# BrauV2_AnalogueOutput.net
KiCad netlist of a schematic drawn in Altium Designer
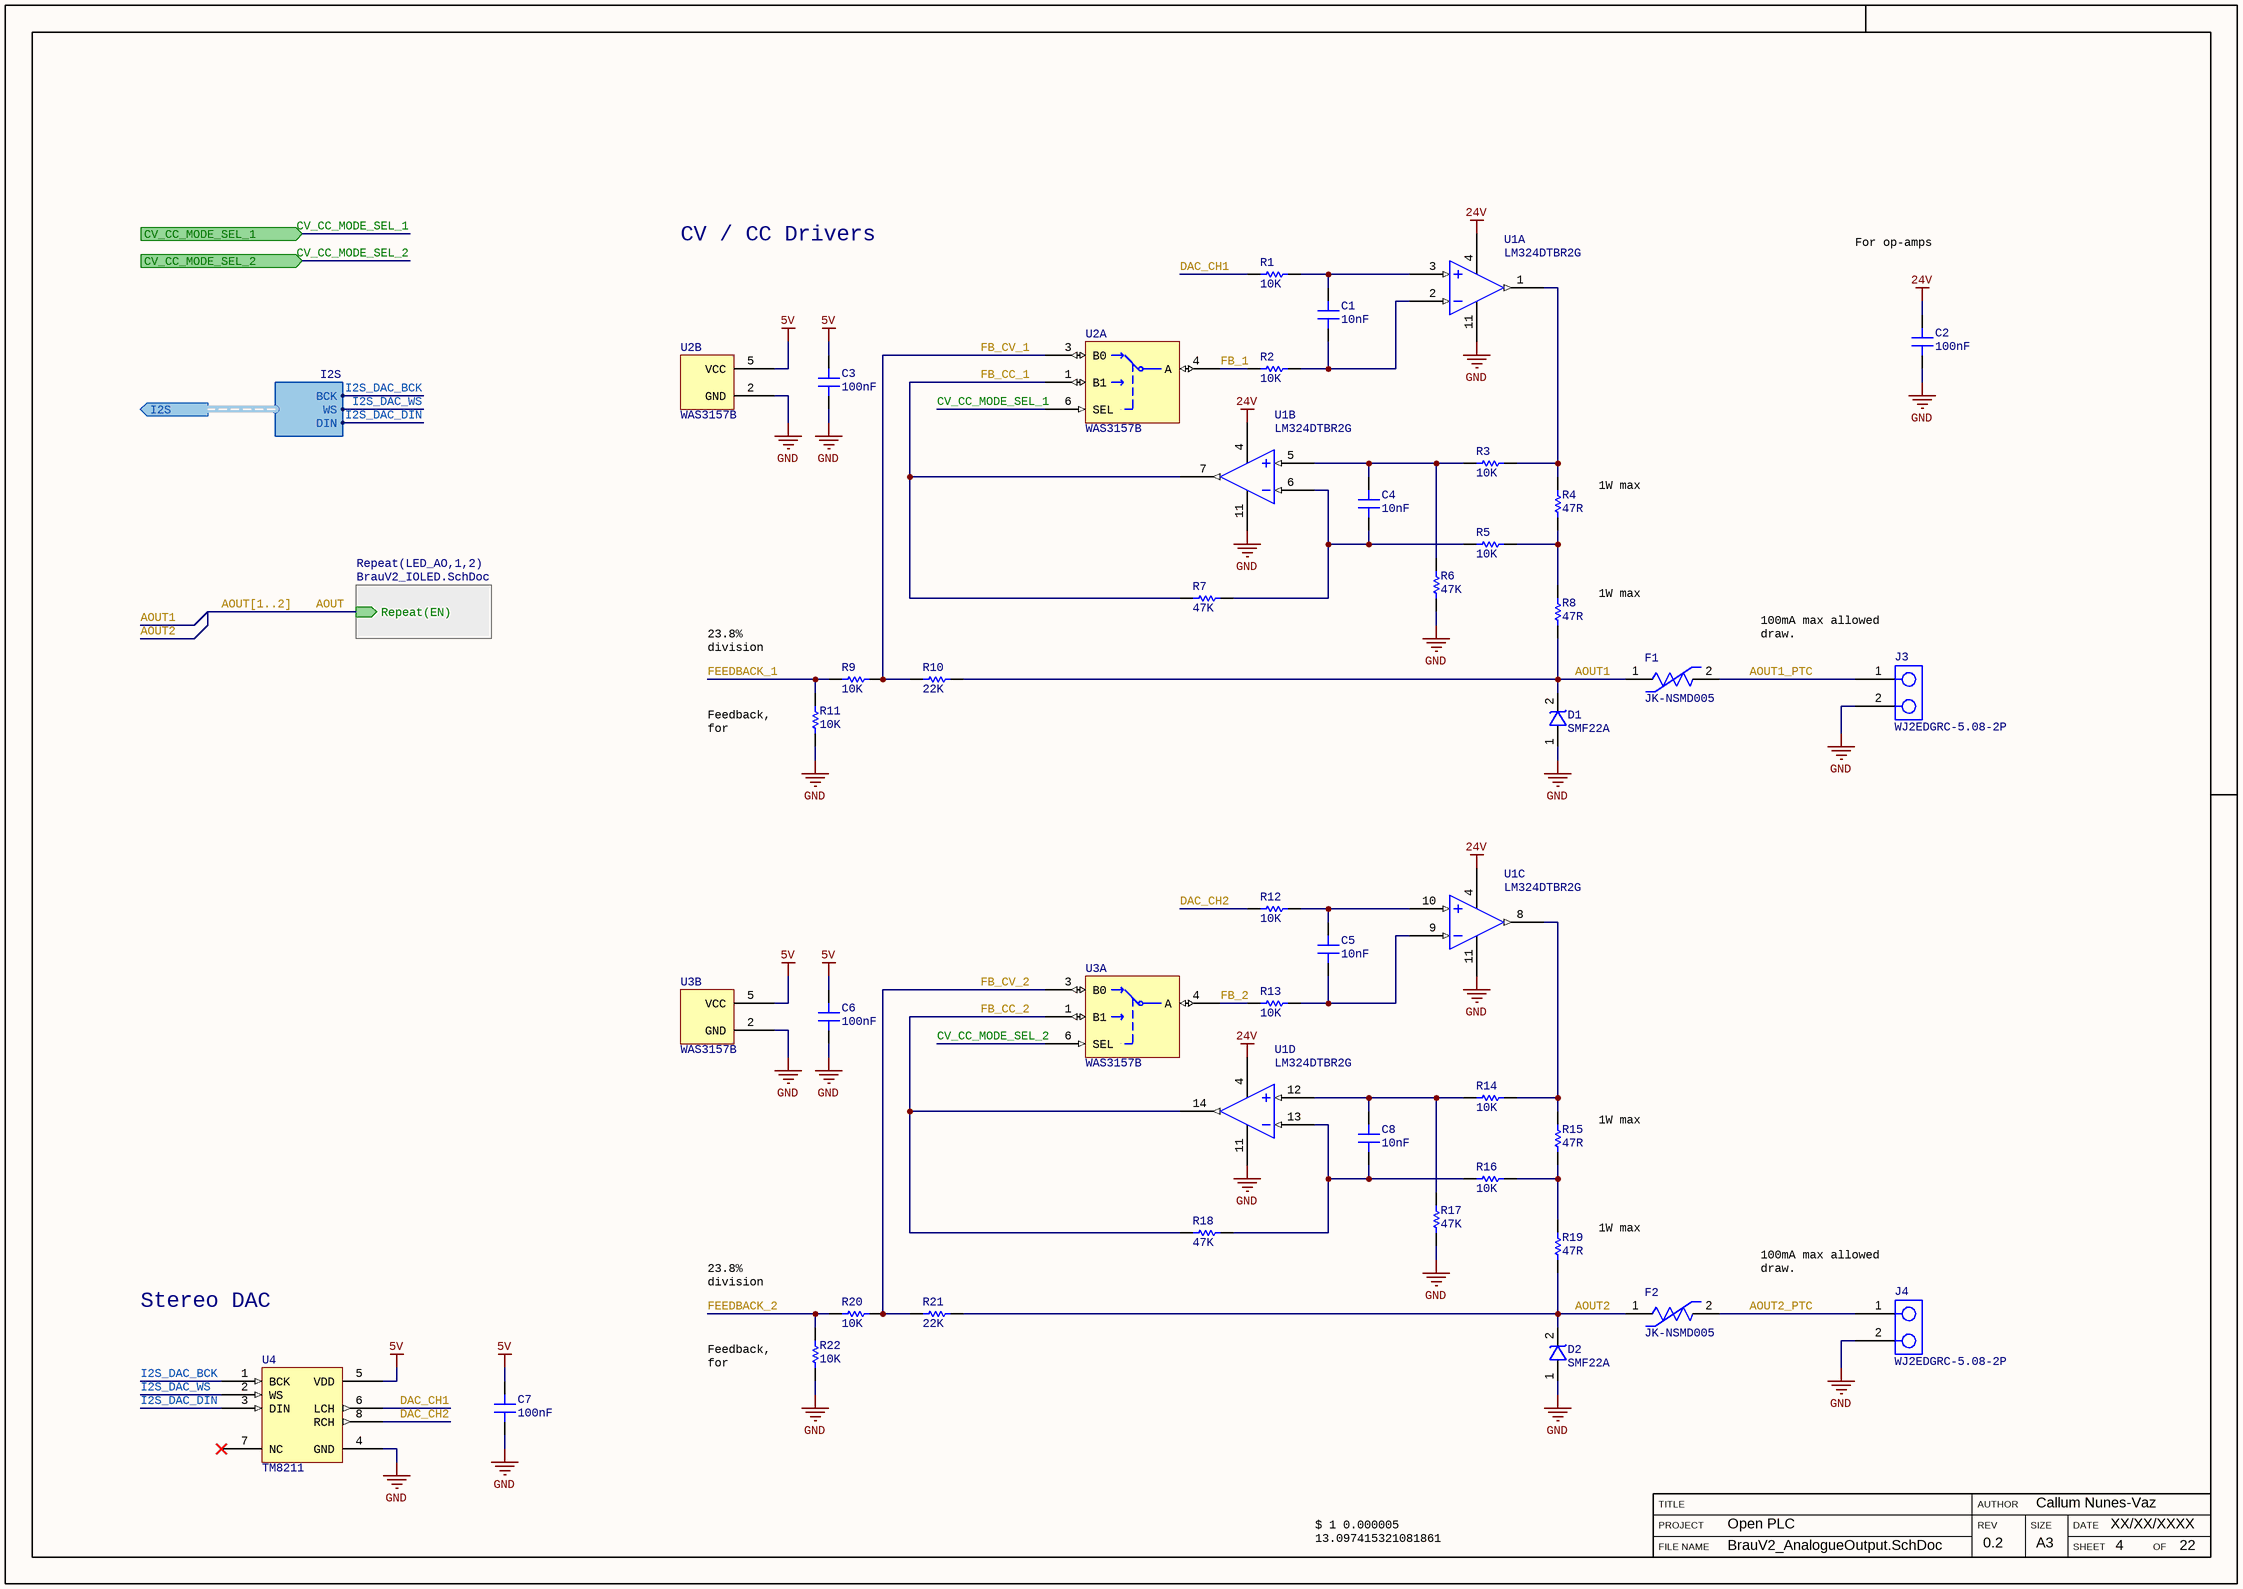
[diagram p0: BrauV2_AnalogueOutput.SchDoc]

(export (version "E")
  (design (tool "Eeschema 10.0.6"))
  (components
    (comp (ref "C1")
      (value "CC0402KRX7R9BB103")
      (footprint "SMD_CAP_0402(1005)_N")
      (description "10nF ±10% 50V X7R 0402 Multilayer Ceramic Capacitors MLCC - SMD/SMT RoHS")
      (fields (field (name "TOLERANCE") "10%") (field (name "CAPACITANCE") "10nF"))
      (libsource (lib "BrauV2_Capacitor") (part "10nF 0402 50V 10%"))
    )
    (comp (ref "C2")
      (value "CC0402KRX5R9BB104")
      (footprint "SMD_CAP_0402(1005)_N")
      (description "100nF ±10% 50V X5R 0402 Multilayer Ceramic Capacitors MLCC - SMD/SMT RoHS")
      (fields (field (name "TOLERANCE") "10%") (field (name "CAPACITANCE") "100nF"))
      (libsource (lib "BrauV2_Capacitor") (part "100nF 0402 50V 10%"))
    )
    (comp (ref "C3")
      (value "CC0402KRX5R6BB104")
      (footprint "SMD_CAP_0402(1005)_N")
      (description "100nF ±10% 10V X5R 0402 Multilayer Ceramic Capacitors MLCC - SMD/SMT RoHS")
      (fields (field (name "TOLERANCE") "10%") (field (name "CAPACITANCE") "100nF"))
      (libsource (lib "BrauV2_Capacitor") (part "100nF 0402 10V 10%"))
    )
    (comp (ref "C4")
      (value "CC0402KRX7R9BB103")
      (footprint "SMD_CAP_0402(1005)_N")
      (description "10nF ±10% 50V X7R 0402 Multilayer Ceramic Capacitors MLCC - SMD/SMT RoHS")
      (fields (field (name "TOLERANCE") "10%") (field (name "CAPACITANCE") "10nF"))
      (libsource (lib "BrauV2_Capacitor") (part "10nF 0402 50V 10%"))
    )
    (comp (ref "C5")
      (value "CC0402KRX7R9BB103")
      (footprint "SMD_CAP_0402(1005)_N")
      (description "10nF ±10% 50V X7R 0402 Multilayer Ceramic Capacitors MLCC - SMD/SMT RoHS")
      (fields (field (name "TOLERANCE") "10%") (field (name "CAPACITANCE") "10nF"))
      (libsource (lib "BrauV2_Capacitor") (part "10nF 0402 50V 10%"))
    )
    (comp (ref "C6")
      (value "CC0402KRX5R6BB104")
      (footprint "SMD_CAP_0402(1005)_N")
      (description "100nF ±10% 10V X5R 0402 Multilayer Ceramic Capacitors MLCC - SMD/SMT RoHS")
      (fields (field (name "TOLERANCE") "10%") (field (name "CAPACITANCE") "100nF"))
      (libsource (lib "BrauV2_Capacitor") (part "100nF 0402 10V 10%"))
    )
    (comp (ref "C7")
      (value "CC0402KRX5R6BB104")
      (footprint "SMD_CAP_0402(1005)_N")
      (description "100nF ±10% 10V X5R 0402 Multilayer Ceramic Capacitors MLCC - SMD/SMT RoHS")
      (fields (field (name "TOLERANCE") "10%") (field (name "CAPACITANCE") "100nF"))
      (libsource (lib "BrauV2_Capacitor") (part "100nF 0402 10V 10%"))
    )
    (comp (ref "C8")
      (value "CC0402KRX7R9BB103")
      (footprint "SMD_CAP_0402(1005)_N")
      (description "10nF ±10% 50V X7R 0402 Multilayer Ceramic Capacitors MLCC - SMD/SMT RoHS")
      (fields (field (name "TOLERANCE") "10%") (field (name "CAPACITANCE") "10nF"))
      (libsource (lib "BrauV2_Capacitor") (part "10nF 0402 50V 10%"))
    )
    (comp (ref "D1")
      (value "SMF22A")
      (footprint "SOD-123FL")
      (description "Unidirectional 22V 24.4V 35.5V 5.6A SOD-123F TVS RoHS")
      (libsource (lib "BrauV2") (part "SMF22A"))
    )
    (comp (ref "D2")
      (value "SMF22A")
      (footprint "SOD-123FL")
      (description "Unidirectional 22V 24.4V 35.5V 5.6A SOD-123F TVS RoHS")
      (libsource (lib "BrauV2") (part "SMF22A"))
    )
    (comp (ref "F1")
      (value "JK-NSMD005")
      (footprint "SMD_RES_1206(3216)_N")
      (description "60V 150mA 1.5s 1206 PTC Resettable Fuses RoHS")
      (libsource (lib "BrauV2_Resistor") (part "JK-NSMD005"))
    )
    (comp (ref "F2")
      (value "JK-NSMD005")
      (footprint "SMD_RES_1206(3216)_N")
      (description "60V 150mA 1.5s 1206 PTC Resettable Fuses RoHS")
      (libsource (lib "BrauV2_Resistor") (part "JK-NSMD005"))
    )
    (comp (ref "J3")
      (value "WJ2EDGRC-5.08-2P")
      (footprint "796638-2")
      (description "Covered（4Sided） 2 1 0.200\"（5.08mm） 2 P=5.08mm Pluggable System Terminal Block RoHS")
      (libsource (lib "BrauV2_Connector") (part "WJ2EDGRC-5.08-2P"))
    )
    (comp (ref "J4")
      (value "WJ2EDGRC-5.08-2P")
      (footprint "796638-2")
      (description "Covered（4Sided） 2 1 0.200\"（5.08mm） 2 P=5.08mm Pluggable System Terminal Block RoHS")
      (libsource (lib "BrauV2_Connector") (part "WJ2EDGRC-5.08-2P"))
    )
    (comp (ref "R1")
      (value "RC0402FR-0710KL")
      (footprint "SMD_RES_0402(1005)_N")
      (description "10kΩ ±1% 1/16W ±100ppm/℃ 0402 Chip Resistor - Surface Mount RoHS")
      (fields (field (name "TOLERANCE") "1%") (field (name "RESISTANCE") "10K"))
      (libsource (lib "BrauV2_Resistor") (part "10K 0402 1% 1/16W"))
    )
    (comp (ref "R2")
      (value "RC0402FR-0710KL")
      (footprint "SMD_RES_0402(1005)_N")
      (description "10kΩ ±1% 1/16W ±100ppm/℃ 0402 Chip Resistor - Surface Mount RoHS")
      (fields (field (name "TOLERANCE") "1%") (field (name "RESISTANCE") "10K"))
      (libsource (lib "BrauV2_Resistor") (part "10K 0402 1% 1/16W"))
    )
    (comp (ref "R3")
      (value "RC0402FR-0710KL")
      (footprint "SMD_RES_0402(1005)_N")
      (description "10kΩ ±1% 1/16W ±100ppm/℃ 0402 Chip Resistor - Surface Mount RoHS")
      (fields (field (name "TOLERANCE") "1%") (field (name "RESISTANCE") "10K"))
      (libsource (lib "BrauV2_Resistor") (part "10K 0402 1% 1/16W"))
    )
    (comp (ref "R4")
      (value "AC2512FK-0747RL")
      (footprint "SMD_RES_2512(6432)_N")
      (description "47Ω ±1% 1W ±100ppm/℃ 2512 Chip Resistor - Surface Mount RoHS")
      (fields (field (name "TOLERANCE") "1%") (field (name "RESISTANCE") "47R"))
      (libsource (lib "BrauV2_Resistor") (part "47R 2512 1% 1W"))
    )
    (comp (ref "R5")
      (value "RC0402FR-0710KL")
      (footprint "SMD_RES_0402(1005)_N")
      (description "10kΩ ±1% 1/16W ±100ppm/℃ 0402 Chip Resistor - Surface Mount RoHS")
      (fields (field (name "TOLERANCE") "1%") (field (name "RESISTANCE") "10K"))
      (libsource (lib "BrauV2_Resistor") (part "10K 0402 1% 1/16W"))
    )
    (comp (ref "R6")
      (value "RC0402FR-0747KL")
      (footprint "SMD_RES_0402(1005)_N")
      (description "47kΩ ±1% 1/16W ±100ppm/℃ 0402 Chip Resistor - Surface Mount RoHS")
      (fields (field (name "TOLERANCE") "1%") (field (name "RESISTANCE") "47K"))
      (libsource (lib "BrauV2_Resistor") (part "47K 0402 1% 1/16W"))
    )
    (comp (ref "R7")
      (value "RC0402FR-0747KL")
      (footprint "SMD_RES_0402(1005)_N")
      (description "47kΩ ±1% 1/16W ±100ppm/℃ 0402 Chip Resistor - Surface Mount RoHS")
      (fields (field (name "TOLERANCE") "1%") (field (name "RESISTANCE") "47K"))
      (libsource (lib "BrauV2_Resistor") (part "47K 0402 1% 1/16W"))
    )
    (comp (ref "R8")
      (value "AC2512FK-0747RL")
      (footprint "SMD_RES_2512(6432)_N")
      (description "47Ω ±1% 1W ±100ppm/℃ 2512 Chip Resistor - Surface Mount RoHS")
      (fields (field (name "TOLERANCE") "1%") (field (name "RESISTANCE") "47R"))
      (libsource (lib "BrauV2_Resistor") (part "47R 2512 1% 1W"))
    )
    (comp (ref "R9")
      (value "RC0402FR-0710KL")
      (footprint "SMD_RES_0402(1005)_N")
      (description "10kΩ ±1% 1/16W ±100ppm/℃ 0402 Chip Resistor - Surface Mount RoHS")
      (fields (field (name "TOLERANCE") "1%") (field (name "RESISTANCE") "10K"))
      (libsource (lib "BrauV2_Resistor") (part "10K 0402 1% 1/16W"))
    )
    (comp (ref "R10")
      (value "RC0402FR-0722KL")
      (footprint "SMD_RES_0402(1005)_N")
      (description "22kΩ ±1% 1/16W ±100ppm/℃ 0402 Chip Resistor - Surface Mount RoHS")
      (fields (field (name "TOLERANCE") "1%") (field (name "RESISTANCE") "22K"))
      (libsource (lib "BrauV2_Resistor") (part "22K 0402 1% 1/16W"))
    )
    (comp (ref "R11")
      (value "RC0402FR-0710KL")
      (footprint "SMD_RES_0402(1005)_N")
      (description "10kΩ ±1% 1/16W ±100ppm/℃ 0402 Chip Resistor - Surface Mount RoHS")
      (fields (field (name "TOLERANCE") "1%") (field (name "RESISTANCE") "10K"))
      (libsource (lib "BrauV2_Resistor") (part "10K 0402 1% 1/16W"))
    )
    (comp (ref "R12")
      (value "RC0402FR-0710KL")
      (footprint "SMD_RES_0402(1005)_N")
      (description "10kΩ ±1% 1/16W ±100ppm/℃ 0402 Chip Resistor - Surface Mount RoHS")
      (fields (field (name "TOLERANCE") "1%") (field (name "RESISTANCE") "10K"))
      (libsource (lib "BrauV2_Resistor") (part "10K 0402 1% 1/16W"))
    )
    (comp (ref "R13")
      (value "RC0402FR-0710KL")
      (footprint "SMD_RES_0402(1005)_N")
      (description "10kΩ ±1% 1/16W ±100ppm/℃ 0402 Chip Resistor - Surface Mount RoHS")
      (fields (field (name "TOLERANCE") "1%") (field (name "RESISTANCE") "10K"))
      (libsource (lib "BrauV2_Resistor") (part "10K 0402 1% 1/16W"))
    )
    (comp (ref "R14")
      (value "RC0402FR-0710KL")
      (footprint "SMD_RES_0402(1005)_N")
      (description "10kΩ ±1% 1/16W ±100ppm/℃ 0402 Chip Resistor - Surface Mount RoHS")
      (fields (field (name "TOLERANCE") "1%") (field (name "RESISTANCE") "10K"))
      (libsource (lib "BrauV2_Resistor") (part "10K 0402 1% 1/16W"))
    )
    (comp (ref "R15")
      (value "AC2512FK-0747RL")
      (footprint "SMD_RES_2512(6432)_N")
      (description "47Ω ±1% 1W ±100ppm/℃ 2512 Chip Resistor - Surface Mount RoHS")
      (fields (field (name "TOLERANCE") "1%") (field (name "RESISTANCE") "47R"))
      (libsource (lib "BrauV2_Resistor") (part "47R 2512 1% 1W"))
    )
    (comp (ref "R16")
      (value "RC0402FR-0710KL")
      (footprint "SMD_RES_0402(1005)_N")
      (description "10kΩ ±1% 1/16W ±100ppm/℃ 0402 Chip Resistor - Surface Mount RoHS")
      (fields (field (name "TOLERANCE") "1%") (field (name "RESISTANCE") "10K"))
      (libsource (lib "BrauV2_Resistor") (part "10K 0402 1% 1/16W"))
    )
    (comp (ref "R17")
      (value "RC0402FR-0747KL")
      (footprint "SMD_RES_0402(1005)_N")
      (description "47kΩ ±1% 1/16W ±100ppm/℃ 0402 Chip Resistor - Surface Mount RoHS")
      (fields (field (name "TOLERANCE") "1%") (field (name "RESISTANCE") "47K"))
      (libsource (lib "BrauV2_Resistor") (part "47K 0402 1% 1/16W"))
    )
    (comp (ref "R18")
      (value "RC0402FR-0747KL")
      (footprint "SMD_RES_0402(1005)_N")
      (description "47kΩ ±1% 1/16W ±100ppm/℃ 0402 Chip Resistor - Surface Mount RoHS")
      (fields (field (name "TOLERANCE") "1%") (field (name "RESISTANCE") "47K"))
      (libsource (lib "BrauV2_Resistor") (part "47K 0402 1% 1/16W"))
    )
    (comp (ref "R19")
      (value "AC2512FK-0747RL")
      (footprint "SMD_RES_2512(6432)_N")
      (description "47Ω ±1% 1W ±100ppm/℃ 2512 Chip Resistor - Surface Mount RoHS")
      (fields (field (name "TOLERANCE") "1%") (field (name "RESISTANCE") "47R"))
      (libsource (lib "BrauV2_Resistor") (part "47R 2512 1% 1W"))
    )
    (comp (ref "R20")
      (value "RC0402FR-0710KL")
      (footprint "SMD_RES_0402(1005)_N")
      (description "10kΩ ±1% 1/16W ±100ppm/℃ 0402 Chip Resistor - Surface Mount RoHS")
      (fields (field (name "TOLERANCE") "1%") (field (name "RESISTANCE") "10K"))
      (libsource (lib "BrauV2_Resistor") (part "10K 0402 1% 1/16W"))
    )
    (comp (ref "R21")
      (value "RC0402FR-0722KL")
      (footprint "SMD_RES_0402(1005)_N")
      (description "22kΩ ±1% 1/16W ±100ppm/℃ 0402 Chip Resistor - Surface Mount RoHS")
      (fields (field (name "TOLERANCE") "1%") (field (name "RESISTANCE") "22K"))
      (libsource (lib "BrauV2_Resistor") (part "22K 0402 1% 1/16W"))
    )
    (comp (ref "R22")
      (value "RC0402FR-0710KL")
      (footprint "SMD_RES_0402(1005)_N")
      (description "10kΩ ±1% 1/16W ±100ppm/℃ 0402 Chip Resistor - Surface Mount RoHS")
      (fields (field (name "TOLERANCE") "1%") (field (name "RESISTANCE") "10K"))
      (libsource (lib "BrauV2_Resistor") (part "10K 0402 1% 1/16W"))
    )
    (comp (ref "U1")
      (value "LM324DTBR2G")
      (footprint "TSSOP-14")
      (description "General Purpose 4 3V ~ 32V, ±1.5V ~ 16V 1MHz 0.6 V/us TSSOP-14 Operational Amplifiers RoHS")
      (libsource (lib "BrauV2_IC") (part "LM324DTBR2G"))
    )
    (comp (ref "U2")
      (value "WAS3157B")
      (footprint "SOT23-6")
      (description "5.5Ω, 400MHz Bandwidth, SPDT Analog Switch SOT23-6")
      (libsource (lib "BrauV2_IC") (part "WAS3157B"))
    )
    (comp (ref "U3")
      (value "WAS3157B")
      (footprint "SOT23-6")
      (description "5.5Ω, 400MHz Bandwidth, SPDT Analog Switch SOT23-6")
      (libsource (lib "BrauV2_IC") (part "WAS3157B"))
    )
    (comp (ref "U4")
      (value "TM8211")
      (footprint "SOIC-8-3.9mm")
      (description "Digital To Analog Converters (DACs) 16bit I2S")
      (libsource (lib "BrauV2_IC") (part "TM8211"))
    )
  )
  (nets
    (net (code "3") (name "/AOUT1") (class "Default")
      (node (ref "D1") (pin "2") (pinfunction "CATHODE_2") (pintype "passive"))
      (node (ref "F1") (pin "1") (pinfunction "1_1") (pintype "passive"))
      (node (ref "R10") (pin "2") (pinfunction "2_2") (pintype "passive"))
      (node (ref "R8") (pin "1") (pinfunction "1_1") (pintype "passive"))
    )
    (net (code "4") (name "/AOUT1_PTC") (class "Default")
      (node (ref "F1") (pin "2") (pinfunction "2_2") (pintype "passive"))
      (node (ref "J3") (pin "1") (pinfunction "1_1") (pintype "passive"))
    )
    (net (code "5") (name "/AOUT2") (class "Default")
      (node (ref "D2") (pin "2") (pinfunction "CATHODE_2") (pintype "passive"))
      (node (ref "F2") (pin "1") (pinfunction "1_1") (pintype "passive"))
      (node (ref "R19") (pin "1") (pinfunction "1_1") (pintype "passive"))
      (node (ref "R21") (pin "2") (pinfunction "2_2") (pintype "passive"))
    )
    (net (code "6") (name "/AOUT2_PTC") (class "Default")
      (node (ref "F2") (pin "2") (pinfunction "2_2") (pintype "passive"))
      (node (ref "J4") (pin "1") (pinfunction "1_1") (pintype "passive"))
    )
    (net (code "8") (name "/CV_CC_MODE_SEL_1") (class "Default")
      (node (ref "U2") (pin "6") (pinfunction "SEL_6") (pintype "input"))
    )
    (net (code "9") (name "/CV_CC_MODE_SEL_2") (class "Default")
      (node (ref "U3") (pin "6") (pinfunction "SEL_6") (pintype "input"))
    )
    (net (code "10") (name "/DAC_CH1") (class "Default")
      (node (ref "R1") (pin "1") (pinfunction "1_1") (pintype "passive"))
      (node (ref "U4") (pin "6") (pinfunction "LCH_6") (pintype "output"))
    )
    (net (code "11") (name "/DAC_CH2") (class "Default")
      (node (ref "R12") (pin "1") (pinfunction "1_1") (pintype "passive"))
      (node (ref "U4") (pin "8") (pinfunction "RCH_8") (pintype "output"))
    )
    (net (code "12") (name "/FB_1") (class "Default")
      (node (ref "R2") (pin "1") (pinfunction "1_1") (pintype "passive"))
      (node (ref "U2") (pin "4") (pinfunction "A_4") (pintype "bidirectional"))
    )
    (net (code "13") (name "/FB_2") (class "Default")
      (node (ref "R13") (pin "1") (pinfunction "1_1") (pintype "passive"))
      (node (ref "U3") (pin "4") (pinfunction "A_4") (pintype "bidirectional"))
    )
    (net (code "14") (name "/FB_CC_1") (class "Default")
      (node (ref "R7") (pin "1") (pinfunction "1_1") (pintype "passive"))
      (node (ref "U1") (pin "7") (pinfunction "VOUT_7") (pintype "output"))
      (node (ref "U2") (pin "1") (pinfunction "B1_1") (pintype "bidirectional"))
    )
    (net (code "15") (name "/FB_CC_2") (class "Default")
      (node (ref "R18") (pin "1") (pinfunction "1_1") (pintype "passive"))
      (node (ref "U1") (pin "14") (pinfunction "VOUT_14") (pintype "output"))
      (node (ref "U3") (pin "1") (pinfunction "B1_1") (pintype "bidirectional"))
    )
    (net (code "16") (name "/FB_CV_1") (class "Default")
      (node (ref "R10") (pin "1") (pinfunction "1_1") (pintype "passive"))
      (node (ref "R9") (pin "1") (pinfunction "1_1") (pintype "passive"))
      (node (ref "U2") (pin "3") (pinfunction "B0_3") (pintype "bidirectional"))
    )
    (net (code "17") (name "/FB_CV_2") (class "Default")
      (node (ref "R20") (pin "1") (pinfunction "1_1") (pintype "passive"))
      (node (ref "R21") (pin "1") (pinfunction "1_1") (pintype "passive"))
      (node (ref "U3") (pin "3") (pinfunction "B0_3") (pintype "bidirectional"))
    )
    (net (code "18") (name "/FEEDBACK_1") (class "Default")
      (node (ref "R11") (pin "2") (pinfunction "2_2") (pintype "passive"))
      (node (ref "R9") (pin "2") (pinfunction "2_2") (pintype "passive"))
    )
    (net (code "19") (name "/FEEDBACK_2") (class "Default")
      (node (ref "R20") (pin "2") (pinfunction "2_2") (pintype "passive"))
      (node (ref "R22") (pin "2") (pinfunction "2_2") (pintype "passive"))
    )
    (net (code "20") (name "/I2S_DAC_BCK") (class "Default")
      (node (ref "U4") (pin "1") (pinfunction "BCK_1") (pintype "input"))
    )
    (net (code "21") (name "/I2S_DAC_DIN") (class "Default")
      (node (ref "U4") (pin "3") (pinfunction "DIN_3") (pintype "input"))
    )
    (net (code "22") (name "/I2S_DAC_WS") (class "Default")
      (node (ref "U4") (pin "2") (pinfunction "WS_2") (pintype "input"))
    )
    (net (code "24") (name "5V") (class "Default")
      (node (ref "C3") (pin "2") (pinfunction "2_2") (pintype "passive"))
      (node (ref "C6") (pin "2") (pinfunction "2_2") (pintype "passive"))
      (node (ref "C7") (pin "2") (pinfunction "2_2") (pintype "passive"))
      (node (ref "U2") (pin "5") (pinfunction "VCC_5") (pintype "power_in"))
      (node (ref "U3") (pin "5") (pinfunction "VCC_5") (pintype "power_in"))
      (node (ref "U4") (pin "5") (pinfunction "VDD_5") (pintype "power_in"))
    )
    (net (code "25") (name "24V") (class "Default")
      (node (ref "C2") (pin "2") (pinfunction "2_2") (pintype "passive"))
      (node (ref "U1") (pin "4") (pinfunction "VDD_4") (pintype "power_in"))
    )
    (net (code "26") (name "GND") (class "Default")
      (node (ref "C2") (pin "1") (pinfunction "1_1") (pintype "passive"))
      (node (ref "C3") (pin "1") (pinfunction "1_1") (pintype "passive"))
      (node (ref "C6") (pin "1") (pinfunction "1_1") (pintype "passive"))
      (node (ref "C7") (pin "1") (pinfunction "1_1") (pintype "passive"))
      (node (ref "D1") (pin "1") (pinfunction "ANODE_1") (pintype "passive"))
      (node (ref "D2") (pin "1") (pinfunction "ANODE_1") (pintype "passive"))
      (node (ref "J3") (pin "2") (pinfunction "2_2") (pintype "passive"))
      (node (ref "J4") (pin "2") (pinfunction "2_2") (pintype "passive"))
      (node (ref "R11") (pin "1") (pinfunction "1_1") (pintype "passive"))
      (node (ref "R17") (pin "1") (pinfunction "1_1") (pintype "passive"))
      (node (ref "R22") (pin "1") (pinfunction "1_1") (pintype "passive"))
      (node (ref "R6") (pin "1") (pinfunction "1_1") (pintype "passive"))
      (node (ref "U1") (pin "11") (pinfunction "VSS_11") (pintype "power_in"))
      (node (ref "U2") (pin "2") (pinfunction "GND_2") (pintype "power_in"))
      (node (ref "U3") (pin "2") (pinfunction "GND_2") (pintype "power_in"))
      (node (ref "U4") (pin "4") (pinfunction "GND_4") (pintype "power_in"))
    )
    (net (code "27") (name "Net-(R4-Pad1)") (class "Default")
      (node (ref "R4") (pin "1") (pinfunction "1_1") (pintype "passive"))
      (node (ref "R5") (pin "2") (pinfunction "2_2") (pintype "passive"))
      (node (ref "R8") (pin "2") (pinfunction "2_2") (pintype "passive"))
    )
    (net (code "28") (name "Net-(R15-Pad1)") (class "Default")
      (node (ref "R15") (pin "1") (pinfunction "1_1") (pintype "passive"))
      (node (ref "R16") (pin "2") (pinfunction "2_2") (pintype "passive"))
      (node (ref "R19") (pin "2") (pinfunction "2_2") (pintype "passive"))
    )
    (net (code "29") (name "Net-(U1A-VIN+)") (class "Default")
      (node (ref "C1") (pin "2") (pinfunction "2_2") (pintype "passive"))
      (node (ref "R1") (pin "2") (pinfunction "2_2") (pintype "passive"))
      (node (ref "U1") (pin "3") (pinfunction "VIN+_3") (pintype "input"))
    )
    (net (code "30") (name "Net-(U1A-VIN-)") (class "Default")
      (node (ref "C1") (pin "1") (pinfunction "1_1") (pintype "passive"))
      (node (ref "R2") (pin "2") (pinfunction "2_2") (pintype "passive"))
      (node (ref "U1") (pin "2") (pinfunction "VIN-_2") (pintype "input"))
    )
    (net (code "31") (name "Net-(U1A-VOUT)") (class "Default")
      (node (ref "R3") (pin "2") (pinfunction "2_2") (pintype "passive"))
      (node (ref "R4") (pin "2") (pinfunction "2_2") (pintype "passive"))
      (node (ref "U1") (pin "1") (pinfunction "VOUT_1") (pintype "output"))
    )
    (net (code "32") (name "Net-(U1B-VIN+)") (class "Default")
      (node (ref "C4") (pin "2") (pinfunction "2_2") (pintype "passive"))
      (node (ref "R3") (pin "1") (pinfunction "1_1") (pintype "passive"))
      (node (ref "R6") (pin "2") (pinfunction "2_2") (pintype "passive"))
      (node (ref "U1") (pin "5") (pinfunction "VIN+_5") (pintype "input"))
    )
    (net (code "33") (name "Net-(U1B-VIN-)") (class "Default")
      (node (ref "C4") (pin "1") (pinfunction "1_1") (pintype "passive"))
      (node (ref "R5") (pin "1") (pinfunction "1_1") (pintype "passive"))
      (node (ref "R7") (pin "2") (pinfunction "2_2") (pintype "passive"))
      (node (ref "U1") (pin "6") (pinfunction "VIN-_6") (pintype "input"))
    )
    (net (code "34") (name "Net-(U1C-VIN+)") (class "Default")
      (node (ref "C5") (pin "2") (pinfunction "2_2") (pintype "passive"))
      (node (ref "R12") (pin "2") (pinfunction "2_2") (pintype "passive"))
      (node (ref "U1") (pin "10") (pinfunction "VIN+_10") (pintype "input"))
    )
    (net (code "35") (name "Net-(U1C-VIN-)") (class "Default")
      (node (ref "C5") (pin "1") (pinfunction "1_1") (pintype "passive"))
      (node (ref "R13") (pin "2") (pinfunction "2_2") (pintype "passive"))
      (node (ref "U1") (pin "9") (pinfunction "VIN-_9") (pintype "input"))
    )
    (net (code "36") (name "Net-(U1C-VOUT)") (class "Default")
      (node (ref "R14") (pin "2") (pinfunction "2_2") (pintype "passive"))
      (node (ref "R15") (pin "2") (pinfunction "2_2") (pintype "passive"))
      (node (ref "U1") (pin "8") (pinfunction "VOUT_8") (pintype "output"))
    )
    (net (code "37") (name "Net-(U1D-VIN+)") (class "Default")
      (node (ref "C8") (pin "2") (pinfunction "2_2") (pintype "passive"))
      (node (ref "R14") (pin "1") (pinfunction "1_1") (pintype "passive"))
      (node (ref "R17") (pin "2") (pinfunction "2_2") (pintype "passive"))
      (node (ref "U1") (pin "12") (pinfunction "VIN+_12") (pintype "input"))
    )
    (net (code "38") (name "Net-(U1D-VIN-)") (class "Default")
      (node (ref "C8") (pin "1") (pinfunction "1_1") (pintype "passive"))
      (node (ref "R16") (pin "1") (pinfunction "1_1") (pintype "passive"))
      (node (ref "R18") (pin "2") (pinfunction "2_2") (pintype "passive"))
      (node (ref "U1") (pin "13") (pinfunction "VIN-_13") (pintype "input"))
    )
    (net (code "39") (name "unconnected-(U4-NC-Pad7)") (class "Default")
      (node (ref "U4") (pin "7") (pinfunction "NC_7") (pintype "passive+no_connect"))
    )
  )
)
